# Input_amplifiers.net
KiCad netlist of a schematic drawn in Altium Designer
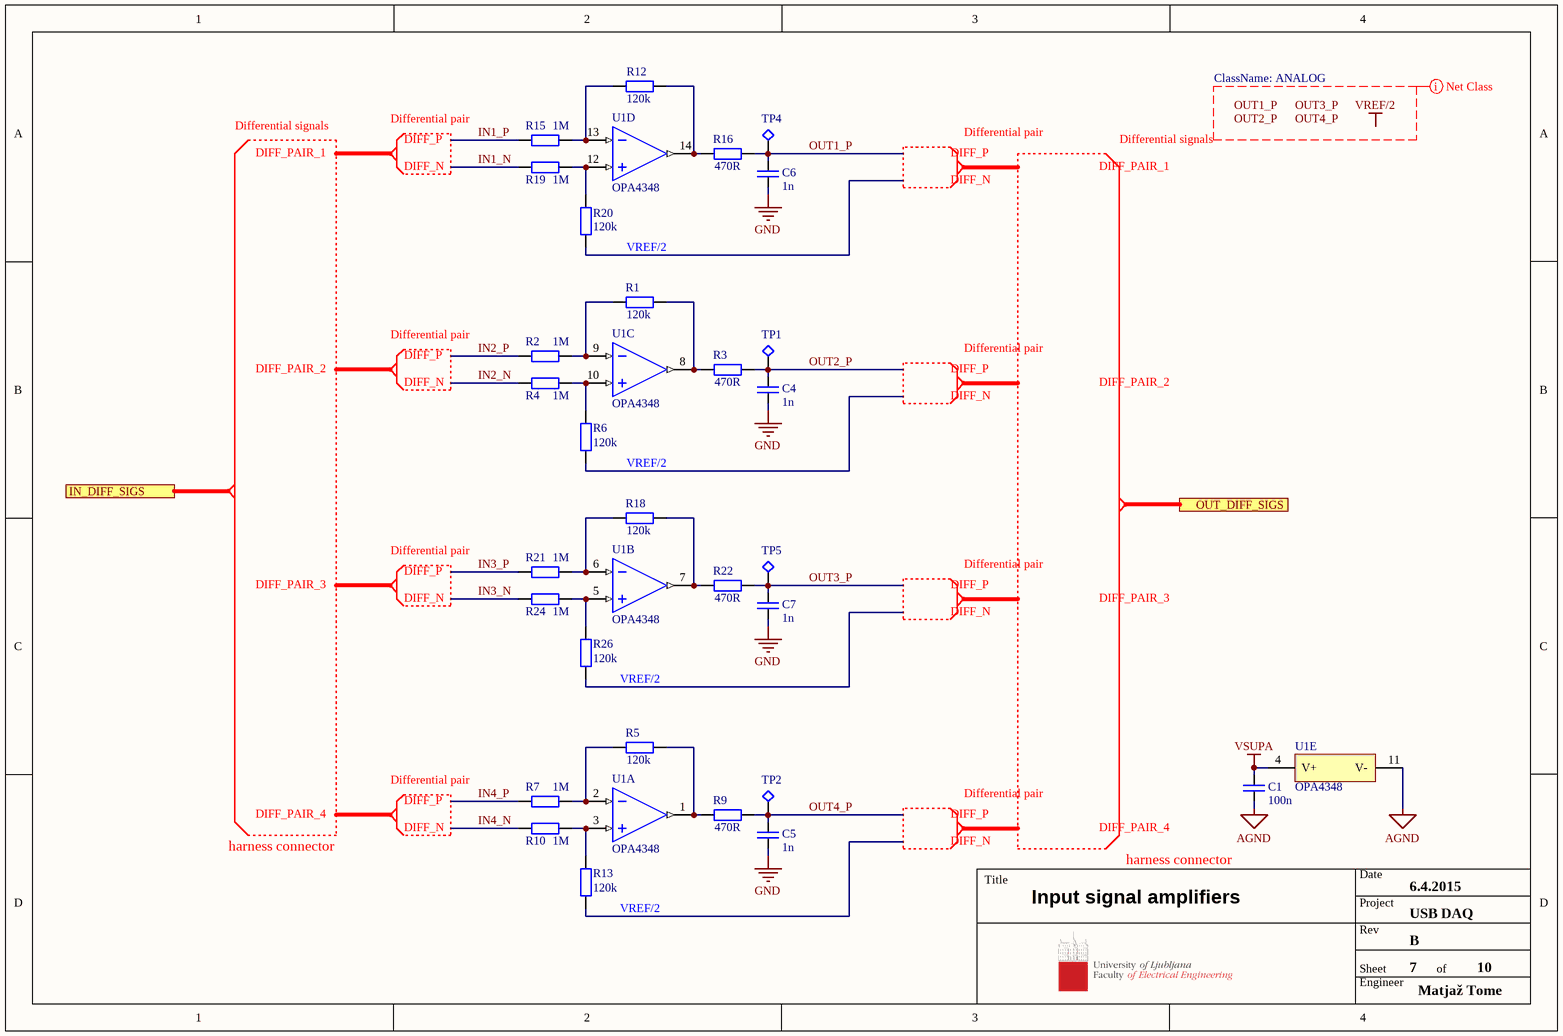
[diagram p0: Input_amplifiers.SchDoc]

(export (version "E")
  (design (tool "Eeschema 10.0.6"))
  (components
    (comp (ref "C1")
      (value "100n")
      (footprint "C_0603")
      (description "Generic capacitor")
      (fields (field (name "Comment") "comment"))
      (libsource (lib "DAQ") (part "Capacitor"))
    )
    (comp (ref "C4")
      (value "1n")
      (footprint "C_0603")
      (description "Generic capacitor")
      (fields (field (name "Comment") "comment"))
      (libsource (lib "DAQ") (part "Capacitor"))
    )
    (comp (ref "C5")
      (value "1n")
      (footprint "C_0603")
      (description "Generic capacitor")
      (fields (field (name "Comment") "comment"))
      (libsource (lib "DAQ") (part "Capacitor"))
    )
    (comp (ref "C6")
      (value "1n")
      (footprint "C_0603")
      (description "Generic capacitor")
      (fields (field (name "Comment") "comment"))
      (libsource (lib "DAQ") (part "Capacitor"))
    )
    (comp (ref "C7")
      (value "1n")
      (footprint "C_0603")
      (description "Generic capacitor")
      (fields (field (name "Comment") "comment"))
      (libsource (lib "DAQ") (part "Capacitor"))
    )
    (comp (ref "R1")
      (value "120k")
      (footprint "R_0603")
      (description "Generic resistor")
      (fields (field (name "Comment") "comment"))
      (libsource (lib "DAQ") (part "Resistor"))
    )
    (comp (ref "R2")
      (value "1M")
      (footprint "R_0603")
      (description "Generic resistor")
      (fields (field (name "Comment") "comment"))
      (libsource (lib "DAQ") (part "Resistor"))
    )
    (comp (ref "R3")
      (value "470R")
      (footprint "R_0603")
      (description "Generic resistor")
      (fields (field (name "Comment") "comment"))
      (libsource (lib "DAQ") (part "Resistor"))
    )
    (comp (ref "R4")
      (value "1M")
      (footprint "R_0603")
      (description "Generic resistor")
      (fields (field (name "Comment") "comment"))
      (libsource (lib "DAQ") (part "Resistor"))
    )
    (comp (ref "R5")
      (value "120k")
      (footprint "R_0603")
      (description "Generic resistor")
      (fields (field (name "Comment") "comment"))
      (libsource (lib "DAQ") (part "Resistor"))
    )
    (comp (ref "R6")
      (value "120k")
      (footprint "R_0603")
      (description "Generic resistor")
      (fields (field (name "Comment") "comment"))
      (libsource (lib "DAQ") (part "Resistor"))
    )
    (comp (ref "R7")
      (value "1M")
      (footprint "R_0603")
      (description "Generic resistor")
      (fields (field (name "Comment") "comment"))
      (libsource (lib "DAQ") (part "Resistor"))
    )
    (comp (ref "R9")
      (value "470R")
      (footprint "R_0603")
      (description "Generic resistor")
      (fields (field (name "Comment") "comment"))
      (libsource (lib "DAQ") (part "Resistor"))
    )
    (comp (ref "R10")
      (value "1M")
      (footprint "R_0603")
      (description "Generic resistor")
      (fields (field (name "Comment") "comment"))
      (libsource (lib "DAQ") (part "Resistor"))
    )
    (comp (ref "R12")
      (value "120k")
      (footprint "R_0603")
      (description "Generic resistor")
      (fields (field (name "Comment") "comment"))
      (libsource (lib "DAQ") (part "Resistor"))
    )
    (comp (ref "R13")
      (value "120k")
      (footprint "R_0603")
      (description "Generic resistor")
      (fields (field (name "Comment") "comment"))
      (libsource (lib "DAQ") (part "Resistor"))
    )
    (comp (ref "R15")
      (value "1M")
      (footprint "R_0603")
      (description "Generic resistor")
      (fields (field (name "Comment") "comment"))
      (libsource (lib "DAQ") (part "Resistor"))
    )
    (comp (ref "R16")
      (value "470R")
      (footprint "R_0603")
      (description "Generic resistor")
      (fields (field (name "Comment") "comment"))
      (libsource (lib "DAQ") (part "Resistor"))
    )
    (comp (ref "R18")
      (value "120k")
      (footprint "R_0603")
      (description "Generic resistor")
      (fields (field (name "Comment") "comment"))
      (libsource (lib "DAQ") (part "Resistor"))
    )
    (comp (ref "R19")
      (value "1M")
      (footprint "R_0603")
      (description "Generic resistor")
      (fields (field (name "Comment") "comment"))
      (libsource (lib "DAQ") (part "Resistor"))
    )
    (comp (ref "R20")
      (value "120k")
      (footprint "R_0603")
      (description "Generic resistor")
      (fields (field (name "Comment") "comment"))
      (libsource (lib "DAQ") (part "Resistor"))
    )
    (comp (ref "R21")
      (value "1M")
      (footprint "R_0603")
      (description "Generic resistor")
      (fields (field (name "Comment") "comment"))
      (libsource (lib "DAQ") (part "Resistor"))
    )
    (comp (ref "R22")
      (value "470R")
      (footprint "R_0603")
      (description "Generic resistor")
      (fields (field (name "Comment") "comment"))
      (libsource (lib "DAQ") (part "Resistor"))
    )
    (comp (ref "R24")
      (value "1M")
      (footprint "R_0603")
      (description "Generic resistor")
      (fields (field (name "Comment") "comment"))
      (libsource (lib "DAQ") (part "Resistor"))
    )
    (comp (ref "R26")
      (value "120k")
      (footprint "R_0603")
      (description "Generic resistor")
      (fields (field (name "Comment") "comment"))
      (libsource (lib "DAQ") (part "Resistor"))
    )
    (comp (ref "TP1")
      (value "testpoint")
      (footprint "TP1_FULL")
      (description "testpoint 1.5mm diameter no hole")
      (fields (field (name "PART NUMBER") "XXC0006"))
      (libsource (lib "DAQ") (part "Test Point"))
    )
    (comp (ref "TP2")
      (value "testpoint")
      (footprint "TP1_FULL")
      (description "testpoint 1.5mm diameter no hole")
      (fields (field (name "PART NUMBER") "XXC0006"))
      (libsource (lib "DAQ") (part "Test Point"))
    )
    (comp (ref "TP4")
      (value "testpoint")
      (footprint "TP1_FULL")
      (description "testpoint 1.5mm diameter no hole")
      (fields (field (name "PART NUMBER") "XXC0006"))
      (libsource (lib "DAQ") (part "Test Point"))
    )
    (comp (ref "TP5")
      (value "testpoint")
      (footprint "TP1_FULL")
      (description "testpoint 1.5mm diameter no hole")
      (fields (field (name "PART NUMBER") "XXC0006"))
      (libsource (lib "DAQ") (part "Test Point"))
    )
    (comp (ref "U1")
      (value "OPA4348")
      (footprint "SOIC14")
      (description "1MHz, 45µA, CMOS, Rail-to-Rail OPERATIONAL AMPLIFIERS Value Line Series")
      (fields (field (name "PART NUMBER") "XOG0008") (field (name "MANUFACTURER") "Texas Instruments"))
      (libsource (lib "DAQ") (part "OPA4348"))
    )
  )
  (nets
    (net (code "5") (name "/IN1_N") (class "Default") (node (ref "R19") (pin "1") (pintype "passive")))
    (net (code "6") (name "/IN1_P") (class "Default") (node (ref "R15") (pin "1") (pintype "passive")))
    (net (code "7") (name "/IN2_N") (class "Default") (node (ref "R4") (pin "1") (pintype "passive")))
    (net (code "8") (name "/IN2_P") (class "Default") (node (ref "R2") (pin "1") (pintype "passive")))
    (net (code "9") (name "/IN3_N") (class "Default") (node (ref "R24") (pin "1") (pintype "passive")))
    (net (code "10") (name "/IN3_P") (class "Default") (node (ref "R21") (pin "1") (pintype "passive")))
    (net (code "11") (name "/IN4_N") (class "Default") (node (ref "R10") (pin "1") (pintype "passive")))
    (net (code "12") (name "/IN4_P") (class "Default") (node (ref "R7") (pin "1") (pintype "passive")))
    (net (code "14") (name "/OUT1_P") (class "Default")
      (node (ref "C6") (pin "1") (pinfunction "1_1") (pintype "passive"))
      (node (ref "R16") (pin "2") (pintype "passive"))
      (node (ref "TP4") (pin "1") (pinfunction "1_1") (pintype "passive"))
    )
    (net (code "15") (name "/OUT2_P") (class "Default")
      (node (ref "C4") (pin "1") (pinfunction "1_1") (pintype "passive"))
      (node (ref "R3") (pin "2") (pintype "passive"))
      (node (ref "TP1") (pin "1") (pinfunction "1_1") (pintype "passive"))
    )
    (net (code "16") (name "/OUT3_P") (class "Default")
      (node (ref "C7") (pin "1") (pinfunction "1_1") (pintype "passive"))
      (node (ref "R22") (pin "2") (pintype "passive"))
      (node (ref "TP5") (pin "1") (pinfunction "1_1") (pintype "passive"))
    )
    (net (code "17") (name "/OUT4_P") (class "Default")
      (node (ref "C5") (pin "1") (pinfunction "1_1") (pintype "passive"))
      (node (ref "R9") (pin "2") (pintype "passive"))
      (node (ref "TP2") (pin "1") (pinfunction "1_1") (pintype "passive"))
    )
    (net (code "19") (name "AGND") (class "Default")
      (node (ref "C1") (pin "1") (pinfunction "1_1") (pintype "passive"))
      (node (ref "U1") (pin "11") (pinfunction "V-_11") (pintype "power_in"))
    )
    (net (code "20") (name "GND") (class "Default")
      (node (ref "C4") (pin "2") (pinfunction "2_2") (pintype "passive"))
      (node (ref "C5") (pin "2") (pinfunction "2_2") (pintype "passive"))
      (node (ref "C6") (pin "2") (pinfunction "2_2") (pintype "passive"))
      (node (ref "C7") (pin "2") (pinfunction "2_2") (pintype "passive"))
    )
    (net (code "21") (name "Net-(U1A-+IN_A)") (class "Default")
      (node (ref "R10") (pin "2") (pintype "passive"))
      (node (ref "R13") (pin "2") (pintype "passive"))
      (node (ref "U1") (pin "3") (pinfunction "+IN_A_3") (pintype "input"))
    )
    (net (code "22") (name "Net-(U1A--IN_A)") (class "Default")
      (node (ref "R5") (pin "1") (pintype "passive"))
      (node (ref "R7") (pin "2") (pintype "passive"))
      (node (ref "U1") (pin "2") (pinfunction "-IN_A_2") (pintype "input"))
    )
    (net (code "23") (name "Net-(U1A-OUT_A)") (class "Default")
      (node (ref "R5") (pin "2") (pintype "passive"))
      (node (ref "R9") (pin "1") (pintype "passive"))
      (node (ref "U1") (pin "1") (pinfunction "OUT_A_1") (pintype "output"))
    )
    (net (code "24") (name "Net-(U1B-+IN_B)") (class "Default")
      (node (ref "R24") (pin "2") (pintype "passive"))
      (node (ref "R26") (pin "2") (pintype "passive"))
      (node (ref "U1") (pin "5") (pinfunction "+IN_B_5") (pintype "input"))
    )
    (net (code "25") (name "Net-(U1B--IN_B)") (class "Default")
      (node (ref "R18") (pin "1") (pintype "passive"))
      (node (ref "R21") (pin "2") (pintype "passive"))
      (node (ref "U1") (pin "6") (pinfunction "-IN_B_6") (pintype "input"))
    )
    (net (code "26") (name "Net-(U1B-OUT_B)") (class "Default")
      (node (ref "R18") (pin "2") (pintype "passive"))
      (node (ref "R22") (pin "1") (pintype "passive"))
      (node (ref "U1") (pin "7") (pinfunction "OUT_B_7") (pintype "output"))
    )
    (net (code "27") (name "Net-(U1C-+IN_C)") (class "Default")
      (node (ref "R4") (pin "2") (pintype "passive"))
      (node (ref "R6") (pin "2") (pintype "passive"))
      (node (ref "U1") (pin "10") (pinfunction "+IN_C_10") (pintype "input"))
    )
    (net (code "28") (name "Net-(U1C--IN_C)") (class "Default")
      (node (ref "R1") (pin "1") (pintype "passive"))
      (node (ref "R2") (pin "2") (pintype "passive"))
      (node (ref "U1") (pin "9") (pinfunction "-IN_C_9") (pintype "input"))
    )
    (net (code "29") (name "Net-(U1C-OUT_C)") (class "Default")
      (node (ref "R1") (pin "2") (pintype "passive"))
      (node (ref "R3") (pin "1") (pintype "passive"))
      (node (ref "U1") (pin "8") (pinfunction "OUT_C_8") (pintype "output"))
    )
    (net (code "30") (name "Net-(U1D-+IN_D)") (class "Default")
      (node (ref "R19") (pin "2") (pintype "passive"))
      (node (ref "R20") (pin "2") (pintype "passive"))
      (node (ref "U1") (pin "12") (pinfunction "+IN_D_12") (pintype "input"))
    )
    (net (code "31") (name "Net-(U1D--IN_D)") (class "Default")
      (node (ref "R12") (pin "1") (pintype "passive"))
      (node (ref "R15") (pin "2") (pintype "passive"))
      (node (ref "U1") (pin "13") (pinfunction "-IN_D_13") (pintype "input"))
    )
    (net (code "32") (name "Net-(U1D-OUT_D)") (class "Default")
      (node (ref "R12") (pin "2") (pintype "passive"))
      (node (ref "R16") (pin "1") (pintype "passive"))
      (node (ref "U1") (pin "14") (pinfunction "OUT_D_14") (pintype "output"))
    )
    (net (code "34") (name "VSUPA") (class "Default")
      (node (ref "C1") (pin "2") (pinfunction "2_2") (pintype "passive"))
      (node (ref "U1") (pin "4") (pinfunction "V+_4") (pintype "power_in"))
    )
    (net (code "35") (name "unconnected-(R6-Pad1)") (class "Default")
      (node (ref "R6") (pin "1") (pintype "passive"))
    )
    (net (code "36") (name "unconnected-(R13-Pad1)") (class "Default")
      (node (ref "R13") (pin "1") (pintype "passive"))
    )
    (net (code "37") (name "unconnected-(R20-Pad1)") (class "Default")
      (node (ref "R20") (pin "1") (pintype "passive"))
    )
    (net (code "38") (name "unconnected-(R26-Pad1)") (class "Default")
      (node (ref "R26") (pin "1") (pintype "passive"))
    )
  )
)
